# Sheet1.net
KiCad netlist of a schematic drawn in Altium Designer
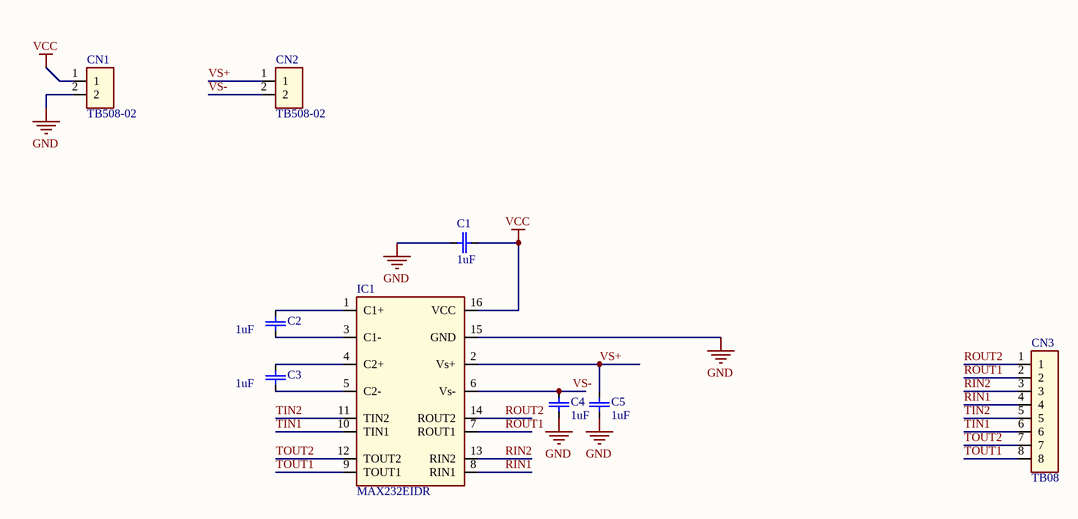
[diagram p0: Sheet1.SchDoc]

(export (version "E")
  (design (tool "Eeschema 10.0.6"))
  (components
    (comp (ref "C1")
      (value "1uF")
      (footprint "C1206")
      (description "Capacitor without polarity")
      (fields (field (name "VOLTAGE") "25V"))
      (libsource (lib "RasUNMSM") (part "Capacitor"))
    )
    (comp (ref "C2")
      (value "1uF")
      (footprint "C0805")
      (description "Capacitor without polarity")
      (fields (field (name "VOLTAGE") "25V"))
      (libsource (lib "RasUNMSM") (part "Capacitor"))
    )
    (comp (ref "C3")
      (value "1uF")
      (footprint "C0805")
      (description "Capacitor without polarity")
      (fields (field (name "VOLTAGE") "25V"))
      (libsource (lib "RasUNMSM") (part "Capacitor"))
    )
    (comp (ref "C4")
      (value "1uF")
      (footprint "C1206")
      (description "Capacitor without polarity")
      (fields (field (name "VOLTAGE") "25V"))
      (libsource (lib "") (part "Capacitor_1"))
    )
    (comp (ref "C5")
      (value "1uF")
      (footprint "C1206")
      (description "Capacitor without polarity")
      (fields (field (name "VOLTAGE") "25V"))
      (libsource (lib "") (part "Capacitor_1"))
    )
    (comp (ref "CN1")
      (value "TB508-02")
      (footprint "TB508-02")
      (description "Terminal Block")
      (libsource (lib "RasUNMSM") (part "TB-02"))
    )
    (comp (ref "CN2")
      (value "TB508-02")
      (footprint "TB508-02")
      (description "Terminal Block")
      (libsource (lib "RasUNMSM") (part "TB-02"))
    )
    (comp (ref "CN3")
      (value "TB08")
      (footprint "TB508-08")
      (description "Terminal Block")
      (libsource (lib "RasUNMSM") (part "TB-08"))
    )
    (comp (ref "IC1")
      (value "MAX232EIDR")
      (footprint "SOIC16-N")
      (description "2/2 Transceiver Full RS232 16-SOIC")
      (libsource (lib "RasUNMSM") (part "MAX232"))
    )
  )
  (nets
    (net (code "1") (name "/RIN1") (class "Default")
      (node (ref "CN3") (pin "4") (pinfunction "4_4") (pintype "passive"))
      (node (ref "IC1") (pin "8") (pinfunction "RIN1_8") (pintype "passive"))
    )
    (net (code "2") (name "/RIN2") (class "Default")
      (node (ref "CN3") (pin "3") (pinfunction "3_3") (pintype "passive"))
      (node (ref "IC1") (pin "13") (pinfunction "RIN2_13") (pintype "passive"))
    )
    (net (code "3") (name "/ROUT1") (class "Default")
      (node (ref "CN3") (pin "2") (pinfunction "2_2") (pintype "passive"))
      (node (ref "IC1") (pin "7") (pinfunction "ROUT1_7") (pintype "passive"))
    )
    (net (code "4") (name "/ROUT2") (class "Default")
      (node (ref "CN3") (pin "1") (pinfunction "1_1") (pintype "passive"))
      (node (ref "IC1") (pin "14") (pinfunction "ROUT2_14") (pintype "passive"))
    )
    (net (code "5") (name "/TIN1") (class "Default")
      (node (ref "CN3") (pin "6") (pinfunction "6_6") (pintype "passive"))
      (node (ref "IC1") (pin "10") (pinfunction "TIN1_10") (pintype "passive"))
    )
    (net (code "6") (name "/TIN2") (class "Default")
      (node (ref "CN3") (pin "5") (pinfunction "5_5") (pintype "passive"))
      (node (ref "IC1") (pin "11") (pinfunction "TIN2_11") (pintype "passive"))
    )
    (net (code "7") (name "/TOUT1") (class "Default")
      (node (ref "CN3") (pin "8") (pinfunction "8_8") (pintype "passive"))
      (node (ref "IC1") (pin "9") (pinfunction "TOUT1_9") (pintype "passive"))
    )
    (net (code "8") (name "/TOUT2") (class "Default")
      (node (ref "CN3") (pin "7") (pinfunction "7_7") (pintype "passive"))
      (node (ref "IC1") (pin "12") (pinfunction "TOUT2_12") (pintype "passive"))
    )
    (net (code "9") (name "/VS+") (class "Default")
      (node (ref "C5") (pin "2") (pinfunction "2_2") (pintype "passive"))
      (node (ref "CN2") (pin "1") (pinfunction "1_1") (pintype "passive"))
      (node (ref "IC1") (pin "2") (pinfunction "Vs+_2") (pintype "passive"))
    )
    (net (code "10") (name "/VS-") (class "Default")
      (node (ref "C4") (pin "2") (pinfunction "2_2") (pintype "passive"))
      (node (ref "CN2") (pin "2") (pinfunction "2_2") (pintype "passive"))
      (node (ref "IC1") (pin "6") (pinfunction "Vs-_6") (pintype "passive"))
    )
    (net (code "11") (name "GND") (class "Default")
      (node (ref "C1") (pin "2") (pinfunction "2_2") (pintype "passive"))
      (node (ref "C4") (pin "1") (pinfunction "1_1") (pintype "passive"))
      (node (ref "C5") (pin "1") (pinfunction "1_1") (pintype "passive"))
      (node (ref "CN1") (pin "2") (pinfunction "2_2") (pintype "passive"))
      (node (ref "IC1") (pin "15") (pinfunction "GND_15") (pintype "passive"))
    )
    (net (code "12") (name "Net-(IC1-C1+)") (class "Default")
      (node (ref "C2") (pin "1") (pinfunction "1_1") (pintype "passive"))
      (node (ref "IC1") (pin "1") (pinfunction "C1+_1") (pintype "passive"))
    )
    (net (code "13") (name "Net-(IC1-C1-)") (class "Default")
      (node (ref "C2") (pin "2") (pinfunction "2_2") (pintype "passive"))
      (node (ref "IC1") (pin "3") (pinfunction "C1-_3") (pintype "passive"))
    )
    (net (code "14") (name "Net-(IC1-C2+)") (class "Default")
      (node (ref "C3") (pin "1") (pinfunction "1_1") (pintype "passive"))
      (node (ref "IC1") (pin "4") (pinfunction "C2+_4") (pintype "passive"))
    )
    (net (code "15") (name "Net-(IC1-C2-)") (class "Default")
      (node (ref "C3") (pin "2") (pinfunction "2_2") (pintype "passive"))
      (node (ref "IC1") (pin "5") (pinfunction "C2-_5") (pintype "passive"))
    )
    (net (code "16") (name "VCC") (class "Default")
      (node (ref "C1") (pin "1") (pinfunction "1_1") (pintype "passive"))
      (node (ref "CN1") (pin "1") (pinfunction "1_1") (pintype "passive"))
      (node (ref "IC1") (pin "16") (pinfunction "VCC_16") (pintype "passive"))
    )
  )
)
